# schbitirme.net
KiCad netlist of a schematic drawn in EAGLE
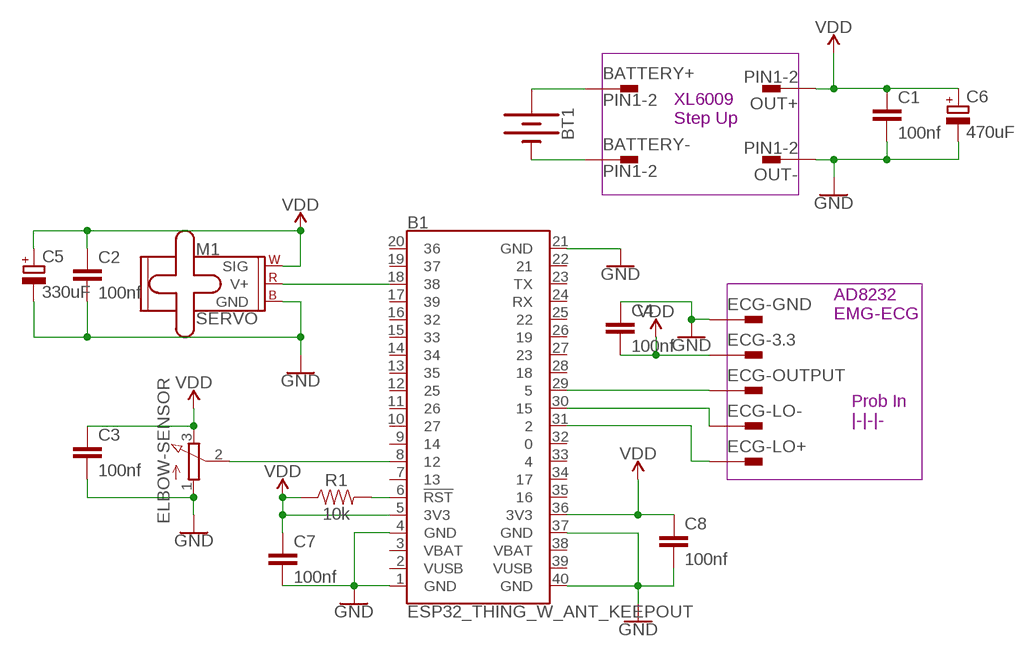
[diagram p0: schematic, sheet 1]

(export (version "E")
  (design (tool "Eeschema 10.0.6"))
  (components
    (comp (ref "B1")
      (value "ESP32_THING_W_ANT_KEEPOUT")
      (footprint "eagle-import:ESP32_THING")
      (libsource (lib "eagle-import") (part "ESP32_THING_W_ANT_KEEPOUT"))
    )
    (comp (ref "BATTERY+")
      (value "PIN1-2")
      (footprint "eagle-import:62221")
      (fields (field (name "MF") "TYCO ELECTRONICS") (field (name "MPN") "62221-1"))
      (libsource (lib "eagle-import") (part "PIN1-2"))
    )
    (comp (ref "BATTERY-")
      (value "PIN1-2")
      (footprint "eagle-import:62221")
      (fields (field (name "MF") "TYCO ELECTRONICS") (field (name "MPN") "62221-1"))
      (libsource (lib "eagle-import") (part "PIN1-2"))
    )
    (comp (ref "BT1")
      (value "BATTERY-18650")
      (footprint "eagle-import:BATTERY_18650-HOLDER")
      (libsource (lib "eagle-import") (part "BATTERY-18650"))
    )
    (comp (ref "C1")
      (value "100nf")
      (footprint "eagle-import:C2.5-3")
      (libsource (lib "eagle-import") (part "C2,5-3"))
    )
    (comp (ref "C2")
      (value "100nf")
      (footprint "eagle-import:C2.5-3")
      (libsource (lib "eagle-import") (part "C2,5-3"))
    )
    (comp (ref "C3")
      (value "100nf")
      (footprint "eagle-import:C2.5-3")
      (libsource (lib "eagle-import") (part "C2,5-3"))
    )
    (comp (ref "C4")
      (value "100nf")
      (footprint "eagle-import:C2.5-3")
      (libsource (lib "eagle-import") (part "C2,5-3"))
    )
    (comp (ref "C5")
      (value "330uF")
      (footprint "eagle-import:PANASONIC_D")
      (libsource (lib "eagle-import") (part "CPOL-EUD"))
    )
    (comp (ref "C6")
      (value "470uF")
      (footprint "eagle-import:PANASONIC_D")
      (libsource (lib "eagle-import") (part "CPOL-EUD"))
    )
    (comp (ref "C7")
      (value "100nf")
      (footprint "eagle-import:C2.5-3")
      (libsource (lib "eagle-import") (part "C2,5-3"))
    )
    (comp (ref "C8")
      (value "100nf")
      (footprint "eagle-import:C2.5-3")
      (libsource (lib "eagle-import") (part "C2,5-3"))
    )
    (comp (ref "ECG-3.3")
      (value "PIN1-2")
      (footprint "eagle-import:62221")
      (fields (field (name "MF") "TYCO ELECTRONICS") (field (name "MPN") "62221-1"))
      (libsource (lib "eagle-import") (part "PIN1-2"))
    )
    (comp (ref "ECG-GND")
      (value "PIN1-2")
      (footprint "eagle-import:62221")
      (fields (field (name "MF") "TYCO ELECTRONICS") (field (name "MPN") "62221-1"))
      (libsource (lib "eagle-import") (part "PIN1-2"))
    )
    (comp (ref "ECG-LO+")
      (value "PIN1-2")
      (footprint "eagle-import:62221")
      (fields (field (name "MF") "TYCO ELECTRONICS") (field (name "MPN") "62221-1"))
      (libsource (lib "eagle-import") (part "PIN1-2"))
    )
    (comp (ref "ECG-LO-")
      (value "PIN1-2")
      (footprint "eagle-import:62221")
      (fields (field (name "MF") "TYCO ELECTRONICS") (field (name "MPN") "62221-1"))
      (libsource (lib "eagle-import") (part "PIN1-2"))
    )
    (comp (ref "ECG-OUTPUT")
      (value "PIN1-2")
      (footprint "eagle-import:62221")
      (fields (field (name "MF") "TYCO ELECTRONICS") (field (name "MPN") "62221-1"))
      (libsource (lib "eagle-import") (part "PIN1-2"))
    )
    (comp (ref "ELBOW-SENSOR")
      (value "3RP/1610N")
      (footprint "eagle-import:3RP_1610N")
      (libsource (lib "eagle-import") (part "3RP/1610N"))
    )
    (comp (ref "M1")
      (value "SERVO")
      (footprint "eagle-import:1X03")
      (libsource (lib "eagle-import") (part "SERVO"))
    )
    (comp (ref "OUT+")
      (value "PIN1-2")
      (footprint "eagle-import:62221")
      (fields (field (name "MF") "TYCO ELECTRONICS") (field (name "MPN") "62221-1"))
      (libsource (lib "eagle-import") (part "PIN1-2"))
    )
    (comp (ref "OUT-")
      (value "PIN1-2")
      (footprint "eagle-import:62221")
      (fields (field (name "MF") "TYCO ELECTRONICS") (field (name "MPN") "62221-1"))
      (libsource (lib "eagle-import") (part "PIN1-2"))
    )
    (comp (ref "R1")
      (value "10k")
      (footprint "eagle-import:0603")
      (libsource (lib "eagle-import") (part "10MOHM-0603-1/10W-5%"))
    )
  )
  (nets
    (net (code "1") (name "GND") (class "Default")
      (node (ref "B1") (pin "1") (pinfunction "GND_1") (pintype "bidirectional"))
      (node (ref "B1") (pin "21") (pinfunction "GND_21") (pintype "bidirectional"))
      (node (ref "B1") (pin "37") (pinfunction "GND_37") (pintype "bidirectional"))
      (node (ref "B1") (pin "4") (pinfunction "GND_4") (pintype "bidirectional"))
      (node (ref "B1") (pin "40") (pinfunction "GND_40") (pintype "bidirectional"))
      (node (ref "C1") (pin "2") (pinfunction "2_2") (pintype "passive"))
      (node (ref "C2") (pin "2") (pinfunction "2_2") (pintype "passive"))
      (node (ref "C3") (pin "2") (pinfunction "2_2") (pintype "passive"))
      (node (ref "C4") (pin "1") (pinfunction "1_1") (pintype "passive"))
      (node (ref "C5") (pin "-") (pinfunction "-_-") (pintype "passive"))
      (node (ref "C6") (pin "-") (pinfunction "-_-") (pintype "passive"))
      (node (ref "C7") (pin "2") (pinfunction "2_2") (pintype "passive"))
      (node (ref "C8") (pin "2") (pinfunction "2_2") (pintype "passive"))
      (node (ref "ECG-GND") (pin "1") (pinfunction "1_1") (pintype "passive"))
      (node (ref "ELBOW-SENSOR") (pin "1") (pinfunction "A_1") (pintype "passive"))
      (node (ref "M1") (pin "3") (pinfunction "GND_3") (pintype "bidirectional"))
      (node (ref "OUT-") (pin "1") (pinfunction "1_1") (pintype "passive"))
    )
    (net (code "2") (name "Net-(B1-2)") (class "Default")
      (node (ref "B1") (pin "31") (pinfunction "2_31") (pintype "bidirectional"))
      (node (ref "ECG-LO+") (pin "1") (pinfunction "1_1") (pintype "passive"))
    )
    (net (code "3") (name "Net-(B1-5)") (class "Default")
      (node (ref "B1") (pin "29") (pinfunction "5_29") (pintype "bidirectional"))
      (node (ref "ECG-OUTPUT") (pin "1") (pinfunction "1_1") (pintype "passive"))
    )
    (net (code "4") (name "Net-(B1-12)") (class "Default")
      (node (ref "B1") (pin "8") (pinfunction "12_8") (pintype "bidirectional"))
      (node (ref "ELBOW-SENSOR") (pin "2") (pinfunction "S_2") (pintype "passive"))
    )
    (net (code "5") (name "Net-(B1-15)") (class "Default")
      (node (ref "B1") (pin "30") (pinfunction "15_30") (pintype "bidirectional"))
      (node (ref "ECG-LO-") (pin "1") (pinfunction "1_1") (pintype "passive"))
    )
    (net (code "6") (name "Net-(B1-38)") (class "Default")
      (node (ref "B1") (pin "18") (pinfunction "38_18") (pintype "bidirectional"))
      (node (ref "M1") (pin "2") (pinfunction "V+_2") (pintype "bidirectional"))
    )
    (net (code "7") (name "Net-(B1-~{RST})") (class "Default")
      (node (ref "B1") (pin "6") (pinfunction "~{RST}_6") (pintype "bidirectional"))
      (node (ref "R1") (pin "2") (pinfunction "2_2") (pintype "passive"))
    )
    (net (code "8") (name "Net-(BT1-+)") (class "Default")
      (node (ref "BATTERY+") (pin "1") (pinfunction "1_1") (pintype "passive"))
      (node (ref "BT1") (pin "PWR@1") (pinfunction "+_PWR@1") (pintype "power_in"))
    )
    (net (code "9") (name "Net-(BT1--)") (class "Default")
      (node (ref "BATTERY-") (pin "1") (pinfunction "1_1") (pintype "passive"))
      (node (ref "BT1") (pin "GND@1") (pinfunction "-_GND@1") (pintype "power_in"))
    )
    (net (code "10") (name "VDD") (class "Default")
      (node (ref "B1") (pin "36") (pinfunction "3V3_36") (pintype "bidirectional"))
      (node (ref "B1") (pin "5") (pinfunction "3V3_5") (pintype "bidirectional"))
      (node (ref "C1") (pin "1") (pinfunction "1_1") (pintype "passive"))
      (node (ref "C2") (pin "1") (pinfunction "1_1") (pintype "passive"))
      (node (ref "C3") (pin "1") (pinfunction "1_1") (pintype "passive"))
      (node (ref "C4") (pin "2") (pinfunction "2_2") (pintype "passive"))
      (node (ref "C5") (pin "+") (pinfunction "+_+") (pintype "passive"))
      (node (ref "C6") (pin "+") (pinfunction "+_+") (pintype "passive"))
      (node (ref "C7") (pin "1") (pinfunction "1_1") (pintype "passive"))
      (node (ref "C8") (pin "1") (pinfunction "1_1") (pintype "passive"))
      (node (ref "ECG-3.3") (pin "1") (pinfunction "1_1") (pintype "passive"))
      (node (ref "ELBOW-SENSOR") (pin "3") (pinfunction "E_3") (pintype "passive"))
      (node (ref "M1") (pin "1") (pinfunction "SIG_1") (pintype "bidirectional"))
      (node (ref "OUT+") (pin "1") (pinfunction "1_1") (pintype "passive"))
      (node (ref "R1") (pin "1") (pinfunction "1_1") (pintype "passive"))
    )
    (net (code "11") (name "unconnected-(B1-0-Pad32)") (class "Default")
      (node (ref "B1") (pin "32") (pinfunction "0_32") (pintype "bidirectional"))
    )
    (net (code "12") (name "unconnected-(B1-4-Pad33)") (class "Default")
      (node (ref "B1") (pin "33") (pinfunction "4_33") (pintype "bidirectional"))
    )
    (net (code "13") (name "unconnected-(B1-13-Pad7)") (class "Default")
      (node (ref "B1") (pin "7") (pinfunction "13_7") (pintype "bidirectional"))
    )
    (net (code "14") (name "unconnected-(B1-14-Pad9)") (class "Default")
      (node (ref "B1") (pin "9") (pinfunction "14_9") (pintype "bidirectional"))
    )
    (net (code "15") (name "unconnected-(B1-16-Pad35)") (class "Default")
      (node (ref "B1") (pin "35") (pinfunction "16_35") (pintype "bidirectional"))
    )
    (net (code "16") (name "unconnected-(B1-17-Pad34)") (class "Default")
      (node (ref "B1") (pin "34") (pinfunction "17_34") (pintype "bidirectional"))
    )
    (net (code "17") (name "unconnected-(B1-18-Pad28)") (class "Default")
      (node (ref "B1") (pin "28") (pinfunction "18_28") (pintype "bidirectional"))
    )
    (net (code "18") (name "unconnected-(B1-19-Pad26)") (class "Default")
      (node (ref "B1") (pin "26") (pinfunction "19_26") (pintype "bidirectional"))
    )
    (net (code "19") (name "unconnected-(B1-21-Pad22)") (class "Default")
      (node (ref "B1") (pin "22") (pinfunction "21_22") (pintype "bidirectional"))
    )
    (net (code "20") (name "unconnected-(B1-22-Pad25)") (class "Default")
      (node (ref "B1") (pin "25") (pinfunction "22_25") (pintype "bidirectional"))
    )
    (net (code "21") (name "unconnected-(B1-23-Pad27)") (class "Default")
      (node (ref "B1") (pin "27") (pinfunction "23_27") (pintype "bidirectional"))
    )
    (net (code "22") (name "unconnected-(B1-25-Pad12)") (class "Default")
      (node (ref "B1") (pin "12") (pinfunction "25_12") (pintype "bidirectional"))
    )
    (net (code "23") (name "unconnected-(B1-26-Pad11)") (class "Default")
      (node (ref "B1") (pin "11") (pinfunction "26_11") (pintype "bidirectional"))
    )
    (net (code "24") (name "unconnected-(B1-27-Pad10)") (class "Default")
      (node (ref "B1") (pin "10") (pinfunction "27_10") (pintype "bidirectional"))
    )
    (net (code "25") (name "unconnected-(B1-32-Pad16)") (class "Default")
      (node (ref "B1") (pin "16") (pinfunction "32_16") (pintype "bidirectional"))
    )
    (net (code "26") (name "unconnected-(B1-33-Pad15)") (class "Default")
      (node (ref "B1") (pin "15") (pinfunction "33_15") (pintype "bidirectional"))
    )
    (net (code "27") (name "unconnected-(B1-34-Pad14)") (class "Default")
      (node (ref "B1") (pin "14") (pinfunction "34_14") (pintype "bidirectional"))
    )
    (net (code "28") (name "unconnected-(B1-35-Pad13)") (class "Default")
      (node (ref "B1") (pin "13") (pinfunction "35_13") (pintype "bidirectional"))
    )
    (net (code "29") (name "unconnected-(B1-36-Pad20)") (class "Default")
      (node (ref "B1") (pin "20") (pinfunction "36_20") (pintype "bidirectional"))
    )
    (net (code "30") (name "unconnected-(B1-37-Pad19)") (class "Default")
      (node (ref "B1") (pin "19") (pinfunction "37_19") (pintype "bidirectional"))
    )
    (net (code "31") (name "unconnected-(B1-39-Pad17)") (class "Default")
      (node (ref "B1") (pin "17") (pinfunction "39_17") (pintype "bidirectional"))
    )
    (net (code "32") (name "unconnected-(B1-RX-Pad24)") (class "Default")
      (node (ref "B1") (pin "24") (pinfunction "RX_24") (pintype "bidirectional"))
    )
    (net (code "33") (name "unconnected-(B1-TX-Pad23)") (class "Default")
      (node (ref "B1") (pin "23") (pinfunction "TX_23") (pintype "bidirectional"))
    )
    (net (code "34") (name "unconnected-(B1-VBAT-Pad3)") (class "Default")
      (node (ref "B1") (pin "3") (pinfunction "VBAT_3") (pintype "bidirectional"))
    )
    (net (code "35") (name "unconnected-(B1-VBAT-Pad38)") (class "Default")
      (node (ref "B1") (pin "38") (pinfunction "VBAT_38") (pintype "bidirectional"))
    )
    (net (code "36") (name "unconnected-(B1-VUSB-Pad2)") (class "Default")
      (node (ref "B1") (pin "2") (pinfunction "VUSB_2") (pintype "bidirectional"))
    )
    (net (code "37") (name "unconnected-(B1-VUSB-Pad39)") (class "Default")
      (node (ref "B1") (pin "39") (pinfunction "VUSB_39") (pintype "bidirectional"))
    )
  )
)
